# TSC_Project_v21.net
KiCad netlist of a schematic drawn in EAGLE
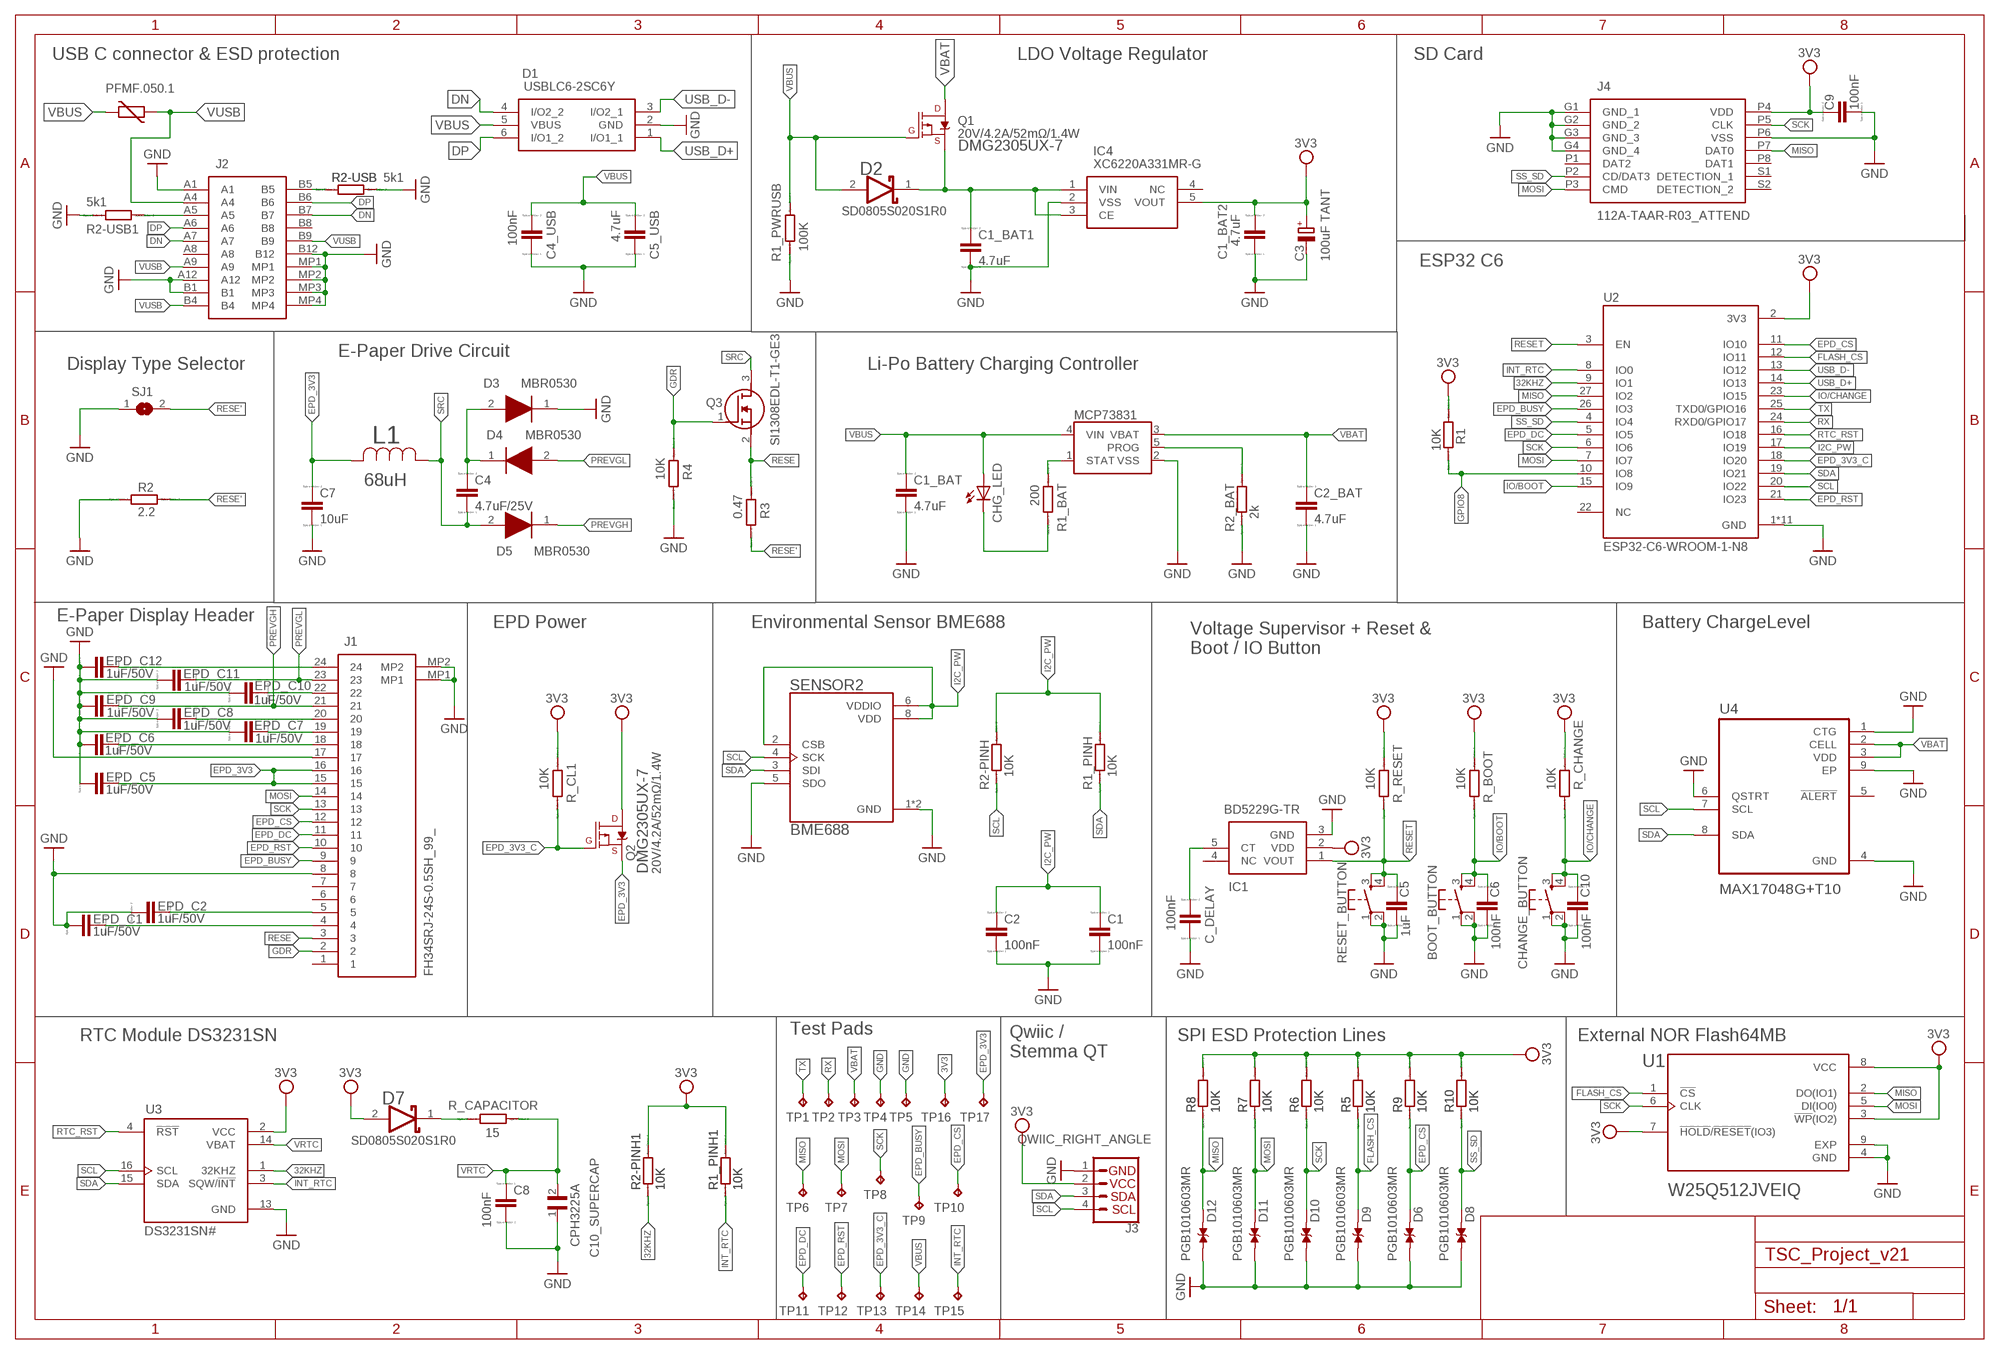
[diagram p0: schematic, sheet 1]

(export (version "E")
  (design (tool "Eeschema 10.0.6"))
  (components
    (comp (ref "BOOT_BUTTON")
      (value "BUTTON_CUSYOMV1")
      (footprint "eagle-import:MYBUTTON")
      (libsource (lib "eagle-import") (part "BUTTON_CUSYOMV1"))
    )
    (comp (ref "C1")
      (value "100nF")
      (footprint "eagle-import:EAGLE-LTSPICE_C0402")
      (libsource (lib "eagle-import") (part "EAGLE-LTSPICE_CC0402"))
    )
    (comp (ref "C1_BAT")
      (value "4.7uF")
      (footprint "eagle-import:EAGLE-LTSPICE_C0402")
      (libsource (lib "eagle-import") (part "EAGLE-LTSPICE_CC0402"))
    )
    (comp (ref "C1_BAT1")
      (value "4.7uF")
      (footprint "eagle-import:EAGLE-LTSPICE_C0402")
      (libsource (lib "eagle-import") (part "EAGLE-LTSPICE_CC0402"))
    )
    (comp (ref "C1_BAT2")
      (value "4.7uF")
      (footprint "eagle-import:EAGLE-LTSPICE_C0402")
      (libsource (lib "eagle-import") (part "EAGLE-LTSPICE_CC0402"))
    )
    (comp (ref "C2")
      (value "100nF")
      (footprint "eagle-import:EAGLE-LTSPICE_C0402")
      (libsource (lib "eagle-import") (part "EAGLE-LTSPICE_CC0402"))
    )
    (comp (ref "C2_BAT")
      (value "4.7uF")
      (footprint "eagle-import:EAGLE-LTSPICE_C0402")
      (libsource (lib "eagle-import") (part "EAGLE-LTSPICE_CC0402"))
    )
    (comp (ref "C3")
      (value "100uF TANT")
      (footprint "eagle-import:RCL_CT3528")
      (libsource (lib "eagle-import") (part "RCL_CPOL-EUCT3528"))
    )
    (comp (ref "C4")
      (value "4.7uF/25V")
      (footprint "eagle-import:EAGLE-LTSPICE_C0402")
      (libsource (lib "eagle-import") (part "EAGLE-LTSPICE_CC0402"))
    )
    (comp (ref "C4_USB")
      (value "100nF")
      (footprint "eagle-import:EAGLE-LTSPICE_C0402")
      (libsource (lib "eagle-import") (part "EAGLE-LTSPICE_CC0402"))
    )
    (comp (ref "C5")
      (value "1uF")
      (footprint "eagle-import:EAGLE-LTSPICE_C0402")
      (libsource (lib "eagle-import") (part "EAGLE-LTSPICE_CC0402"))
    )
    (comp (ref "C5_USB")
      (value "4.7uF")
      (footprint "eagle-import:EAGLE-LTSPICE_C0402")
      (libsource (lib "eagle-import") (part "EAGLE-LTSPICE_CC0402"))
    )
    (comp (ref "C6")
      (value "100nF")
      (footprint "eagle-import:EAGLE-LTSPICE_C0402")
      (libsource (lib "eagle-import") (part "EAGLE-LTSPICE_CC0402"))
    )
    (comp (ref "C7")
      (value "10uF")
      (footprint "eagle-import:EAGLE-LTSPICE_C0402")
      (libsource (lib "eagle-import") (part "EAGLE-LTSPICE_CC0402"))
    )
    (comp (ref "C8")
      (value "100nF")
      (footprint "eagle-import:EAGLE-LTSPICE_C0402")
      (libsource (lib "eagle-import") (part "EAGLE-LTSPICE_CC0402"))
    )
    (comp (ref "C9")
      (value "100nF")
      (footprint "eagle-import:EAGLE-LTSPICE_C0402")
      (libsource (lib "eagle-import") (part "EAGLE-LTSPICE_CC0402"))
    )
    (comp (ref "C10")
      (value "100nF")
      (footprint "eagle-import:EAGLE-LTSPICE_C0402")
      (libsource (lib "eagle-import") (part "EAGLE-LTSPICE_CC0402"))
    )
    (comp (ref "C10_SUPERCAP")
      (value "CPH3225A")
      (footprint "eagle-import:CAPCP3225X100N")
      (fields (field (name "MF") "Seiko Instruments"))
      (libsource (lib "eagle-import") (part "CPH3225A"))
    )
    (comp (ref "CHANGE_BUTTON")
      (value "BUTTON_CUSYOMV1")
      (footprint "eagle-import:MYBUTTON")
      (libsource (lib "eagle-import") (part "BUTTON_CUSYOMV1"))
    )
    (comp (ref "CHG_LED")
      (value "ADAFRUIT_LEDCHIP-LED0603")
      (footprint "eagle-import:ADAFRUIT_CHIP-LED0603")
      (libsource (lib "eagle-import") (part "ADAFRUIT_LEDCHIP-LED0603"))
    )
    (comp (ref "C_DELAY")
      (value "100nF")
      (footprint "eagle-import:EAGLE-LTSPICE_C0402")
      (libsource (lib "eagle-import") (part "EAGLE-LTSPICE_CC0402"))
    )
    (comp (ref "D1")
      (value "USBLC6-2SC6Y")
      (footprint "eagle-import:SOT95P280X145-6N")
      (fields (field (name "MF") "STMicroelectronics"))
      (libsource (lib "eagle-import") (part "USBLC6-2SC6Y"))
    )
    (comp (ref "D2")
      (value "ESP32_WROVER_AVX---SD0805S020S1R0_AVX_SD0805S020S1R0_0_0AVX_SD0805S020S1R0_0_0")
      (footprint "eagle-import:ESP32_WROVER_AVX---SD0805S020S1R0_AVX_SD0805S020S1R0_0")
      (fields
        (field (name "DIGIKEY_PART_NUMBER") "478-7800-1-ND")
        (field (name "MF") "AVX")
        (field (name "MOUSER_PART_NUMBER") "581-SD0805S020S1R0")
        (field (name "SD0805S020S1R0") "SD0805S020S1R0")
      )
      (libsource (lib "eagle-import") (part "ESP32_WROVER_AVX---SD0805S020S1R0_AVX_SD0805S020S1R0_0_0AVX_SD0805S020S1R0_0_0"))
    )
    (comp (ref "D3")
      (value "MBR0530")
      (footprint "eagle-import:SOD3716X135N")
      (fields (field (name "MF") "ON Semiconductor"))
      (libsource (lib "eagle-import") (part "MBR0530"))
    )
    (comp (ref "D4")
      (value "MBR0530")
      (footprint "eagle-import:SOD3716X135N")
      (fields (field (name "MF") "ON Semiconductor"))
      (libsource (lib "eagle-import") (part "MBR0530"))
    )
    (comp (ref "D5")
      (value "MBR0530")
      (footprint "eagle-import:SOD3716X135N")
      (fields (field (name "MF") "ON Semiconductor"))
      (libsource (lib "eagle-import") (part "MBR0530"))
    )
    (comp (ref "D6")
      (value "PGB1010603MR")
      (footprint "eagle-import:DIOC1608X36N")
      (fields (field (name "MF") "Littelfuse Inc."))
      (libsource (lib "eagle-import") (part "PGB1010603MR"))
    )
    (comp (ref "D7")
      (value "ESP32_WROVER_AVX---SD0805S020S1R0_AVX_SD0805S020S1R0_0_0AVX_SD0805S020S1R0_0_0")
      (footprint "eagle-import:ESP32_WROVER_AVX---SD0805S020S1R0_AVX_SD0805S020S1R0_0")
      (fields
        (field (name "DIGIKEY_PART_NUMBER") "478-7800-1-ND")
        (field (name "MF") "AVX")
        (field (name "MOUSER_PART_NUMBER") "581-SD0805S020S1R0")
        (field (name "DIODE") "SD0805S020S1R0")
      )
      (libsource (lib "eagle-import") (part "ESP32_WROVER_AVX---SD0805S020S1R0_AVX_SD0805S020S1R0_0_0AVX_SD0805S020S1R0_0_0"))
    )
    (comp (ref "D8")
      (value "PGB1010603MR")
      (footprint "eagle-import:DIOC1608X36N")
      (fields (field (name "MF") "Littelfuse Inc."))
      (libsource (lib "eagle-import") (part "PGB1010603MR"))
    )
    (comp (ref "D9")
      (value "PGB1010603MR")
      (footprint "eagle-import:DIOC1608X36N")
      (fields (field (name "MF") "Littelfuse Inc."))
      (libsource (lib "eagle-import") (part "PGB1010603MR"))
    )
    (comp (ref "D10")
      (value "PGB1010603MR")
      (footprint "eagle-import:DIOC1608X36N")
      (fields (field (name "MF") "Littelfuse Inc."))
      (libsource (lib "eagle-import") (part "PGB1010603MR"))
    )
    (comp (ref "D11")
      (value "PGB1010603MR")
      (footprint "eagle-import:DIOC1608X36N")
      (fields (field (name "MF") "Littelfuse Inc."))
      (libsource (lib "eagle-import") (part "PGB1010603MR"))
    )
    (comp (ref "D12")
      (value "PGB1010603MR")
      (footprint "eagle-import:DIOC1608X36N")
      (fields (field (name "MF") "Littelfuse Inc."))
      (libsource (lib "eagle-import") (part "PGB1010603MR"))
    )
    (comp (ref "EPD_C1")
      (value "1uF/50V")
      (footprint "eagle-import:EAGLE-LTSPICE_C0402")
      (libsource (lib "eagle-import") (part "EAGLE-LTSPICE_CC0402"))
    )
    (comp (ref "EPD_C2")
      (value "1uF/50V")
      (footprint "eagle-import:EAGLE-LTSPICE_C0402")
      (libsource (lib "eagle-import") (part "EAGLE-LTSPICE_CC0402"))
    )
    (comp (ref "EPD_C5")
      (value "1uF/50V")
      (footprint "eagle-import:EAGLE-LTSPICE_C0402")
      (libsource (lib "eagle-import") (part "EAGLE-LTSPICE_CC0402"))
    )
    (comp (ref "EPD_C6")
      (value "1uF/50V")
      (footprint "eagle-import:EAGLE-LTSPICE_C0402")
      (libsource (lib "eagle-import") (part "EAGLE-LTSPICE_CC0402"))
    )
    (comp (ref "EPD_C7")
      (value "1uF/50V")
      (footprint "eagle-import:EAGLE-LTSPICE_C0402")
      (libsource (lib "eagle-import") (part "EAGLE-LTSPICE_CC0402"))
    )
    (comp (ref "EPD_C8")
      (value "1uF/50V")
      (footprint "eagle-import:EAGLE-LTSPICE_C0402")
      (libsource (lib "eagle-import") (part "EAGLE-LTSPICE_CC0402"))
    )
    (comp (ref "EPD_C9")
      (value "1uF/50V")
      (footprint "eagle-import:EAGLE-LTSPICE_C0402")
      (libsource (lib "eagle-import") (part "EAGLE-LTSPICE_CC0402"))
    )
    (comp (ref "EPD_C10")
      (value "1uF/50V")
      (footprint "eagle-import:EAGLE-LTSPICE_C0402")
      (libsource (lib "eagle-import") (part "EAGLE-LTSPICE_CC0402"))
    )
    (comp (ref "EPD_C11")
      (value "1uF/50V")
      (footprint "eagle-import:EAGLE-LTSPICE_C0402")
      (libsource (lib "eagle-import") (part "EAGLE-LTSPICE_CC0402"))
    )
    (comp (ref "EPD_C12")
      (value "1uF/50V")
      (footprint "eagle-import:EAGLE-LTSPICE_C0402")
      (libsource (lib "eagle-import") (part "EAGLE-LTSPICE_CC0402"))
    )
    (comp (ref "IC1")
      (value "BD5229G-TR")
      (footprint "eagle-import:SOT95P280X125-5N")
      (fields (field (name "MOUSER_PART_NUMBER") "755-BD5229G-TR"))
      (libsource (lib "eagle-import") (part "BD5229G-TR"))
    )
    (comp (ref "IC4")
      (value "XC6220A331MR-G")
      (footprint "eagle-import:SOT95P280X120-5N")
      (fields (field (name "MOUSER_PART_NUMBER") "865-XC6220A331MR-G"))
      (libsource (lib "eagle-import") (part "XC6220A331MR-G"))
    )
    (comp (ref "J1")
      (value "FH34SRJ-24S-0.5SH_99_")
      (footprint "eagle-import:FH34SRJ24S05SH99")
      (fields
        (field (name "MANUFACTURER_PART_NUMBER") "FH34SRJ-24S-0.5SH(99)")
        (field (name "MOUSER_PART_NUMBER") "798-FH34SRJ24S05SH99")
      )
      (libsource (lib "eagle-import") (part "FH34SRJ-24S-0.5SH_99_"))
    )
    (comp (ref "J2")
      (value "SAMACSYS_PARTS_USB4110-GF-A")
      (footprint "eagle-import:SAMACSYS_PARTS_USB4110GFA")
      (fields
        (field (name "MANUFACTURER_PART_NUMBER") "USB4110-GF-A")
        (field (name "MOUSER_PART_NUMBER") "640-USB4110-GF-A")
      )
      (libsource (lib "eagle-import") (part "SAMACSYS_PARTS_USB4110-GF-A"))
    )
    (comp (ref "J3")
      (value "QWIIC_RIGHT_ANGLE")
      (footprint "eagle-import:JST04_1MM_RA")
      (libsource (lib "eagle-import") (part "QWIIC_CONNECTORJS-1MM"))
    )
    (comp (ref "J4")
      (value "112A-TAAR-R03_ATTEND")
      (footprint "eagle-import:112ATAARR03ATTEND")
      (fields (field (name "MANUFACTURER_PART_NUMBER") "112A-TAAR-R03 ATTEND"))
      (libsource (lib "eagle-import") (part "112A-TAAR-R03_ATTEND"))
    )
    (comp (ref "L1")
      (value "744043680IND_4828-WE-TPC_WRE")
      (footprint "eagle-import:IND_4828-WE-TPC_WRE")
      (fields
        (field (name "MANUFACTURER_PART_NUMBER") "744043680")
        (field (name "L1") "68uH")
        (field (name "COPYRIGHT") "Copyright (C) 2024 Ultra Librarian. All rights reserved.")
      )
      (libsource (lib "eagle-import") (part "744043680IND_4828-WE-TPC_WRE"))
    )
    (comp (ref "MCP73831")
      (value "ESP32_WROVER_SPARKFUN-IC-POWER_MCP73831")
      (footprint "eagle-import:ESP32_WROVER_SPARKFUN-IC-POWER_SOT23-5")
      (libsource (lib "eagle-import") (part "ESP32_WROVER_SPARKFUN-IC-POWER_MCP73831"))
    )
    (comp (ref "PFMF.050.1")
      (value "ESP32C6_VARISTORCN1812")
      (footprint "eagle-import:ESP32C6_VARISTOR_CT_CN1812")
      (libsource (lib "eagle-import") (part "ESP32C6_VARISTORCN1812"))
    )
    (comp (ref "Q1")
      (value "20V/4.2A/52mΩ/1.4W")
      (footprint "eagle-import:ESP32_WROVER_SPARKFUN-DISCRETESEMI_SOT23-3")
      (libsource (lib "eagle-import") (part "ESP32_WROVER_SPARKFUN-DISCRETESEMI_MOSFET_PCH-DMG2305UX-7"))
    )
    (comp (ref "Q2")
      (value "20V/4.2A/52mΩ/1.4W")
      (footprint "eagle-import:ESP32_WROVER_SPARKFUN-DISCRETESEMI_SOT23-3")
      (libsource (lib "eagle-import") (part "ESP32_WROVER_SPARKFUN-DISCRETESEMI_MOSFET_PCH-DMG2305UX-7"))
    )
    (comp (ref "Q3")
      (value "SI1308EDL-T1-GE3")
      (footprint "eagle-import:SOT65P210X110-3N")
      (fields (field (name "MF") "Vishay Siliconix"))
      (libsource (lib "eagle-import") (part "SI1308EDL-T1-GE3"))
    )
    (comp (ref "R1")
      (value "10K")
      (footprint "eagle-import:ESP32_WROVER_EAGLE-LTSPICE_R0402")
      (libsource (lib "eagle-import") (part "ESP32_WROVER_EAGLE-LTSPICE_RR0402"))
    )
    (comp (ref "R1_BAT")
      (value "200")
      (footprint "eagle-import:ESP32_WROVER_EAGLE-LTSPICE_R0402")
      (libsource (lib "eagle-import") (part "ESP32_WROVER_EAGLE-LTSPICE_RR0402"))
    )
    (comp (ref "R1_PINH")
      (value "10K")
      (footprint "eagle-import:ESP32_WROVER_EAGLE-LTSPICE_R0402")
      (libsource (lib "eagle-import") (part "ESP32_WROVER_EAGLE-LTSPICE_RR0402"))
    )
    (comp (ref "R1_PINH1")
      (value "10K")
      (footprint "eagle-import:ESP32_WROVER_EAGLE-LTSPICE_R0402")
      (libsource (lib "eagle-import") (part "ESP32_WROVER_EAGLE-LTSPICE_RR0402"))
    )
    (comp (ref "R1_PWRUSB")
      (value "100K")
      (footprint "eagle-import:ESP32_WROVER_EAGLE-LTSPICE_R0402")
      (libsource (lib "eagle-import") (part "ESP32_WROVER_EAGLE-LTSPICE_RR0402"))
    )
    (comp (ref "R2")
      (value "2.2")
      (footprint "eagle-import:ESP32_WROVER_EAGLE-LTSPICE_R0402")
      (libsource (lib "eagle-import") (part "ESP32_WROVER_EAGLE-LTSPICE_RR0402"))
    )
    (comp (ref "R2-PINH")
      (value "10K")
      (footprint "eagle-import:ESP32_WROVER_EAGLE-LTSPICE_R0402")
      (libsource (lib "eagle-import") (part "ESP32_WROVER_EAGLE-LTSPICE_RR0402"))
    )
    (comp (ref "R2-PINH1")
      (value "10K")
      (footprint "eagle-import:ESP32_WROVER_EAGLE-LTSPICE_R0402")
      (libsource (lib "eagle-import") (part "ESP32_WROVER_EAGLE-LTSPICE_RR0402"))
    )
    (comp (ref "R2-USB")
      (value "5k1")
      (footprint "eagle-import:ESP32_WROVER_EAGLE-LTSPICE_R0402")
      (libsource (lib "eagle-import") (part "ESP32_WROVER_EAGLE-LTSPICE_RR0402"))
    )
    (comp (ref "R2-USB1")
      (value "5k1")
      (footprint "eagle-import:ESP32_WROVER_EAGLE-LTSPICE_R0402")
      (libsource (lib "eagle-import") (part "ESP32_WROVER_EAGLE-LTSPICE_RR0402"))
    )
    (comp (ref "R2_BAT")
      (value "2k")
      (footprint "eagle-import:ESP32_WROVER_EAGLE-LTSPICE_R0402")
      (libsource (lib "eagle-import") (part "ESP32_WROVER_EAGLE-LTSPICE_RR0402"))
    )
    (comp (ref "R3")
      (value "0.47")
      (footprint "eagle-import:ESP32_WROVER_EAGLE-LTSPICE_R0402")
      (libsource (lib "eagle-import") (part "ESP32_WROVER_EAGLE-LTSPICE_RR0402"))
    )
    (comp (ref "R4")
      (value "10K")
      (footprint "eagle-import:ESP32_WROVER_EAGLE-LTSPICE_R0402")
      (libsource (lib "eagle-import") (part "ESP32_WROVER_EAGLE-LTSPICE_RR0402"))
    )
    (comp (ref "R5")
      (value "10K")
      (footprint "eagle-import:ESP32_WROVER_EAGLE-LTSPICE_R0402")
      (libsource (lib "eagle-import") (part "ESP32_WROVER_EAGLE-LTSPICE_RR0402"))
    )
    (comp (ref "R6")
      (value "10K")
      (footprint "eagle-import:ESP32_WROVER_EAGLE-LTSPICE_R0402")
      (libsource (lib "eagle-import") (part "ESP32_WROVER_EAGLE-LTSPICE_RR0402"))
    )
    (comp (ref "R7")
      (value "10K")
      (footprint "eagle-import:ESP32_WROVER_EAGLE-LTSPICE_R0402")
      (libsource (lib "eagle-import") (part "ESP32_WROVER_EAGLE-LTSPICE_RR0402"))
    )
    (comp (ref "R8")
      (value "10K")
      (footprint "eagle-import:ESP32_WROVER_EAGLE-LTSPICE_R0402")
      (libsource (lib "eagle-import") (part "ESP32_WROVER_EAGLE-LTSPICE_RR0402"))
    )
    (comp (ref "R9")
      (value "10K")
      (footprint "eagle-import:ESP32_WROVER_EAGLE-LTSPICE_R0402")
      (libsource (lib "eagle-import") (part "ESP32_WROVER_EAGLE-LTSPICE_RR0402"))
    )
    (comp (ref "R10")
      (value "10K")
      (footprint "eagle-import:ESP32_WROVER_EAGLE-LTSPICE_R0402")
      (libsource (lib "eagle-import") (part "ESP32_WROVER_EAGLE-LTSPICE_RR0402"))
    )
    (comp (ref "RESET_BUTTON")
      (value "BUTTON_CUSYOMV1")
      (footprint "eagle-import:MYBUTTON")
      (libsource (lib "eagle-import") (part "BUTTON_CUSYOMV1"))
    )
    (comp (ref "R_BOOT")
      (value "10K")
      (footprint "eagle-import:ESP32_WROVER_EAGLE-LTSPICE_R0402")
      (libsource (lib "eagle-import") (part "ESP32_WROVER_EAGLE-LTSPICE_RR0402"))
    )
    (comp (ref "R_CAPACITOR")
      (value "15")
      (footprint "eagle-import:ESP32_WROVER_EAGLE-LTSPICE_R0402")
      (libsource (lib "eagle-import") (part "ESP32_WROVER_EAGLE-LTSPICE_RR0402"))
    )
    (comp (ref "R_CHANGE")
      (value "10K")
      (footprint "eagle-import:ESP32_WROVER_EAGLE-LTSPICE_R0402")
      (libsource (lib "eagle-import") (part "ESP32_WROVER_EAGLE-LTSPICE_RR0402"))
    )
    (comp (ref "R_CL1")
      (value "10K")
      (footprint "eagle-import:ESP32_WROVER_EAGLE-LTSPICE_R0402")
      (libsource (lib "eagle-import") (part "ESP32_WROVER_EAGLE-LTSPICE_RR0402"))
    )
    (comp (ref "R_RESET")
      (value "10K")
      (footprint "eagle-import:ESP32_WROVER_EAGLE-LTSPICE_R0402")
      (libsource (lib "eagle-import") (part "ESP32_WROVER_EAGLE-LTSPICE_RR0402"))
    )
    (comp (ref "SENSOR2")
      (value "ESP32_WROVER_BME680_BME680")
      (footprint "eagle-import:ESP32_WROVER_BME680_PSON80P300X300X100-8N")
      (fields
        (field (name "MF") "Bosch Sensortec")
        (field (name "MP") "BME680")
        (field (name "MP1") "BME688")
      )
      (libsource (lib "eagle-import") (part "ESP32_WROVER_BME680_BME680"))
    )
    (comp (ref "SJ1") (value "SJ") (footprint "eagle-import:SJ") (libsource (lib "eagle-import") (part "SJ")))
    (comp (ref "TP1")
      (value "TPTP20R")
      (footprint "eagle-import:TP20R")
      (libsource (lib "eagle-import") (part "TPTP20R"))
    )
    (comp (ref "TP2")
      (value "TPTP20R")
      (footprint "eagle-import:TP20R")
      (libsource (lib "eagle-import") (part "TPTP20R"))
    )
    (comp (ref "TP3")
      (value "TPTP20R")
      (footprint "eagle-import:TP20R")
      (libsource (lib "eagle-import") (part "TPTP20R"))
    )
    (comp (ref "TP4")
      (value "TPTP20R")
      (footprint "eagle-import:TP20R")
      (libsource (lib "eagle-import") (part "TPTP20R"))
    )
    (comp (ref "TP5")
      (value "TPTP20R")
      (footprint "eagle-import:TP20R")
      (libsource (lib "eagle-import") (part "TPTP20R"))
    )
    (comp (ref "TP6")
      (value "TPTP20R")
      (footprint "eagle-import:TP20R")
      (libsource (lib "eagle-import") (part "TPTP20R"))
    )
    (comp (ref "TP7")
      (value "TPTP20R")
      (footprint "eagle-import:TP20R")
      (libsource (lib "eagle-import") (part "TPTP20R"))
    )
    (comp (ref "TP8")
      (value "TPTP20R")
      (footprint "eagle-import:TP20R")
      (libsource (lib "eagle-import") (part "TPTP20R"))
    )
    (comp (ref "TP9")
      (value "TPTP20R")
      (footprint "eagle-import:TP20R")
      (libsource (lib "eagle-import") (part "TPTP20R"))
    )
    (comp (ref "TP10")
      (value "TPTP20R")
      (footprint "eagle-import:TP20R")
      (libsource (lib "eagle-import") (part "TPTP20R"))
    )
    (comp (ref "TP11")
      (value "TPTP20R")
      (footprint "eagle-import:TP20R")
      (libsource (lib "eagle-import") (part "TPTP20R"))
    )
    (comp (ref "TP12")
      (value "TPTP20R")
      (footprint "eagle-import:TP20R")
      (libsource (lib "eagle-import") (part "TPTP20R"))
    )
    (comp (ref "TP13")
      (value "TPTP20R")
      (footprint "eagle-import:TP20R")
      (libsource (lib "eagle-import") (part "TPTP20R"))
    )
    (comp (ref "TP14")
      (value "TPTP20R")
      (footprint "eagle-import:TP20R")
      (libsource (lib "eagle-import") (part "TPTP20R"))
    )
    (comp (ref "TP15")
      (value "TPTP20R")
      (footprint "eagle-import:TP20R")
      (libsource (lib "eagle-import") (part "TPTP20R"))
    )
    (comp (ref "TP16")
      (value "TPTP20R")
      (footprint "eagle-import:TP20R")
      (libsource (lib "eagle-import") (part "TPTP20R"))
    )
    (comp (ref "TP17")
      (value "TPTP20R")
      (footprint "eagle-import:TP20R")
      (libsource (lib "eagle-import") (part "TPTP20R"))
    )
    (comp (ref "U1")
      (value "W25Q512JVEIQ")
      (footprint "eagle-import:SON127P600X800X80-9N")
      (fields (field (name "MF") "Winbond Electronics"))
      (libsource (lib "eagle-import") (part "W25Q512JVEIQ"))
    )
    (comp (ref "U2")
      (value "ESP32-C6-WROOM-1-N8")
      (footprint "eagle-import:XCVR_ESP32-C6-WROOM-1-N8")
      (fields (field (name "MF") "Espressif Systems"))
      (libsource (lib "eagle-import") (part "ESP32-C6-WROOM-1-N8"))
    )
    (comp (ref "U3")
      (value "DS3231SN#")
      (footprint "eagle-import:SOIC127P1032X265-16N")
      (fields (field (name "MF") "Analog Devices"))
      (libsource (lib "eagle-import") (part "DS3231SN#"))
    )
    (comp (ref "U4")
      (value "MAX17048G+T10")
      (footprint "eagle-import:SON50P200X200X80-9N")
      (fields (field (name "MF") "Analog Devices"))
      (libsource (lib "eagle-import") (part "MAX17048G+T10"))
    )
  )
  (nets
    (net (code "1") (name "3V3") (class "Default")
      (node (ref "C1_BAT2") (pin "2") (pinfunction "2_2") (pintype "passive"))
      (node (ref "C3") (pin "+") (pinfunction "+_+") (pintype "passive"))
      (node (ref "C9") (pin "2") (pinfunction "2_2") (pintype "passive"))
      (node (ref "D7") (pin "2") (pinfunction "ANODE_2") (pintype "bidirectional"))
      (node (ref "IC1") (pin "2") (pinfunction "VDD_2") (pintype "bidirectional"))
      (node (ref "IC4") (pin "5") (pinfunction "VOUT_5") (pintype "bidirectional"))
      (node (ref "J3") (pin "2") (pinfunction "2_2") (pintype "power_in"))
      (node (ref "J4") (pin "P4") (pinfunction "VDD_P4") (pintype "bidirectional"))
      (node (ref "Q2") (pin "3") (pinfunction "D_3") (pintype "bidirectional"))
      (node (ref "R1") (pin "1") (pinfunction "1_1") (pintype "passive"))
      (node (ref "R10") (pin "2") (pinfunction "2_2") (pintype "passive"))
      (node (ref "R1_PINH1") (pin "2") (pinfunction "2_2") (pintype "passive"))
      (node (ref "R2-PINH1") (pin "2") (pinfunction "2_2") (pintype "passive"))
      (node (ref "R5") (pin "2") (pinfunction "2_2") (pintype "passive"))
      (node (ref "R6") (pin "2") (pinfunction "2_2") (pintype "passive"))
      (node (ref "R7") (pin "2") (pinfunction "2_2") (pintype "passive"))
      (node (ref "R8") (pin "2") (pinfunction "2_2") (pintype "passive"))
      (node (ref "R9") (pin "2") (pinfunction "2_2") (pintype "passive"))
      (node (ref "R_BOOT") (pin "2") (pinfunction "2_2") (pintype "passive"))
      (node (ref "R_CHANGE") (pin "2") (pinfunction "2_2") (pintype "passive"))
      (node (ref "R_CL1") (pin "2") (pinfunction "2_2") (pintype "passive"))
      (node (ref "R_RESET") (pin "2") (pinfunction "2_2") (pintype "passive"))
      (node (ref "TP16") (pin "TP") (pinfunction "TP_TP") (pintype "input"))
      (node (ref "U1") (pin "3") (pinfunction "~{WP}(IO2)_3") (pintype "bidirectional"))
      (node (ref "U1") (pin "7") (pinfunction "~{HOLD}/~{RESET}(IO3)_7") (pintype "bidirectional"))
      (node (ref "U1") (pin "8") (pinfunction "VCC_8") (pintype "power_in"))
      (node (ref "U2") (pin "2") (pinfunction "3V3_2") (pintype "power_in"))
      (node (ref "U3") (pin "2") (pinfunction "VCC_2") (pintype "power_in"))
    )
    (net (code "2") (name "32KHZ") (class "Default")
      (node (ref "R2-PINH1") (pin "1") (pinfunction "1_1") (pintype "passive"))
      (node (ref "U2") (pin "9") (pinfunction "IO1_9") (pintype "bidirectional"))
      (node (ref "U3") (pin "1") (pinfunction "32KHZ_1") (pintype "output"))
    )
    (net (code "3") (name "DN") (class "Default")
      (node (ref "D1") (pin "4") (pinfunction "I/O2_2_4") (pintype "bidirectional"))
      (node (ref "J2") (pin "A7") (pinfunction "A7_A7") (pintype "bidirectional"))
      (node (ref "J2") (pin "B7") (pinfunction "B7_B7") (pintype "bidirectional"))
    )
    (net (code "4") (name "DP") (class "Default")
      (node (ref "D1") (pin "6") (pinfunction "I/O1_2_6") (pintype "bidirectional"))
      (node (ref "J2") (pin "A6") (pinfunction "A6_A6") (pintype "bidirectional"))
      (node (ref "J2") (pin "B6") (pinfunction "B6_B6") (pintype "bidirectional"))
    )
    (net (code "5") (name "EPD_3V3") (class "Default")
      (node (ref "C7") (pin "2") (pinfunction "2_2") (pintype "passive"))
      (node (ref "EPD_C5") (pin "1") (pinfunction "1_1") (pintype "passive"))
      (node (ref "J1") (pin "15") (pinfunction "15_15") (pintype "bidirectional"))
      (node (ref "J1") (pin "16") (pinfunction "16_16") (pintype "bidirectional"))
      (node (ref "L1") (pin "2") (pinfunction "2_2") (pintype "passive"))
      (node (ref "Q2") (pin "2") (pinfunction "S_2") (pintype "bidirectional"))
      (node (ref "TP17") (pin "TP") (pinfunction "TP_TP") (pintype "input"))
    )
    (net (code "6") (name "EPD_3V3_C") (class "Default")
      (node (ref "Q2") (pin "1") (pinfunction "G_1") (pintype "bidirectional"))
      (node (ref "R_CL1") (pin "1") (pinfunction "1_1") (pintype "passive"))
      (node (ref "TP13") (pin "TP") (pinfunction "TP_TP") (pintype "input"))
      (node (ref "U2") (pin "18") (pinfunction "IO20_18") (pintype "bidirectional"))
    )
    (net (code "7") (name "EPD_BUSY") (class "Default")
      (node (ref "J1") (pin "9") (pinfunction "9_9") (pintype "bidirectional"))
      (node (ref "TP9") (pin "TP") (pinfunction "TP_TP") (pintype "input"))
      (node (ref "U2") (pin "26") (pinfunction "IO3_26") (pintype "bidirectional"))
    )
    (net (code "8") (name "EPD_CS") (class "Default")
      (node (ref "D6") (pin "2") (pinfunction "2_2") (pintype "passive"))
      (node (ref "J1") (pin "12") (pinfunction "12_12") (pintype "bidirectional"))
      (node (ref "R9") (pin "1") (pinfunction "1_1") (pintype "passive"))
      (node (ref "TP10") (pin "TP") (pinfunction "TP_TP") (pintype "input"))
      (node (ref "U2") (pin "11") (pinfunction "IO10_11") (pintype "bidirectional"))
    )
    (net (code "9") (name "EPD_DC") (class "Default")
      (node (ref "J1") (pin "11") (pinfunction "11_11") (pintype "bidirectional"))
      (node (ref "TP11") (pin "TP") (pinfunction "TP_TP") (pintype "input"))
      (node (ref "U2") (pin "5") (pinfunction "IO5_5") (pintype "bidirectional"))
    )
    (net (code "10") (name "EPD_RST") (class "Default")
      (node (ref "J1") (pin "10") (pinfunction "10_10") (pintype "bidirectional"))
      (node (ref "TP12") (pin "TP") (pinfunction "TP_TP") (pintype "input"))
      (node (ref "U2") (pin "21") (pinfunction "IO23_21") (pintype "bidirectional"))
    )
    (net (code "11") (name "FLASH_CS") (class "Default")
      (node (ref "D9") (pin "2") (pinfunction "2_2") (pintype "passive"))
      (node (ref "R5") (pin "1") (pinfunction "1_1") (pintype "passive"))
      (node (ref "U1") (pin "1") (pinfunction "~{CS}_1") (pintype "input"))
      (node (ref "U2") (pin "12") (pinfunction "IO11_12") (pintype "bidirectional"))
    )
    (net (code "12") (name "GDR") (class "Default")
      (node (ref "J1") (pin "2") (pinfunction "2_2") (pintype "bidirectional"))
      (node (ref "Q3") (pin "1") (pinfunction "G_1") (pintype "bidirectional"))
      (node (ref "R4") (pin "2") (pinfunction "2_2") (pintype "passive"))
    )
    (net (code "13") (name "GND") (class "Default")
      (node (ref "BOOT_BUTTON") (pin "1") (pinfunction "1_1") (pintype "passive"))
      (node (ref "BOOT_BUTTON") (pin "2") (pinfunction "2_2") (pintype "passive"))
      (node (ref "C1") (pin "1") (pinfunction "1_1") (pintype "passive"))
      (node (ref "C10") (pin "1") (pinfunction "1_1") (pintype "passive"))
      (node (ref "C10_SUPERCAP") (pin "1") (pinfunction "1_1") (pintype "passive"))
      (node (ref "C1_BAT") (pin "1") (pinfunction "1_1") (pintype "passive"))
      (node (ref "C1_BAT1") (pin "1") (pinfunction "1_1") (pintype "passive"))
      (node (ref "C1_BAT2") (pin "1") (pinfunction "1_1") (pintype "passive"))
      (node (ref "C2") (pin "1") (pinfunction "1_1") (pintype "passive"))
      (node (ref "C2_BAT") (pin "1") (pinfunction "1_1") (pintype "passive"))
      (node (ref "C3") (pin "-") (pinfunction "-_-") (pintype "passive"))
      (node (ref "C4_USB") (pin "1") (pinfunction "1_1") (pintype "passive"))
      (node (ref "C5") (pin "1") (pinfunction "1_1") (pintype "passive"))
      (node (ref "C5_USB") (pin "1") (pinfunction "1_1") (pintype "passive"))
      (node (ref "C6") (pin "1") (pinfunction "1_1") (pintype "passive"))
      (node (ref "C7") (pin "1") (pinfunction "1_1") (pintype "passive"))
      (node (ref "C8") (pin "2") (pinfunction "2_2") (pintype "passive"))
      (node (ref "C9") (pin "1") (pinfunction "1_1") (pintype "passive"))
      (node (ref "CHANGE_BUTTON") (pin "1") (pinfunction "1_1") (pintype "passive"))
      (node (ref "CHANGE_BUTTON") (pin "2") (pinfunction "2_2") (pintype "passive"))
      (node (ref "C_DELAY") (pin "1") (pinfunction "1_1") (pintype "passive"))
      (node (ref "D1") (pin "2") (pinfunction "GND_2") (pintype "bidirectional"))
      (node (ref "D10") (pin "1") (pinfunction "1_1") (pintype "passive"))
      (node (ref "D11") (pin "1") (pinfunction "1_1") (pintype "passive"))
      (node (ref "D12") (pin "1") (pinfunction "1_1") (pintype "passive"))
      (node (ref "D3") (pin "1") (pinfunction "K_1") (pintype "bidirectional"))
      (node (ref "D6") (pin "1") (pinfunction "1_1") (pintype "passive"))
      (node (ref "D8") (pin "1") (pinfunction "1_1") (pintype "passive"))
      (node (ref "D9") (pin "1") (pinfunction "1_1") (pintype "passive"))
      (node (ref "EPD_C1") (pin "2") (pinfunction "2_2") (pintype "passive"))
      (node (ref "EPD_C10") (pin "2") (pinfunction "2_2") (pintype "passive"))
      (node (ref "EPD_C11") (pin "2") (pinfunction "2_2") (pintype "passive"))
      (node (ref "EPD_C12") (pin "2") (pinfunction "2_2") (pintype "passive"))
      (node (ref "EPD_C2") (pin "2") (pinfunction "2_2") (pintype "passive"))
      (node (ref "EPD_C5") (pin "2") (pinfunction "2_2") (pintype "passive"))
      (node (ref "EPD_C6") (pin "2") (pinfunction "2_2") (pintype "passive"))
      (node (ref "EPD_C7") (pin "2") (pinfunction "2_2") (pintype "passive"))
      (node (ref "EPD_C8") (pin "2") (pinfunction "2_2") (pintype "passive"))
      (node (ref "EPD_C9") (pin "2") (pinfunction "2_2") (pintype "passive"))
      (node (ref "IC1") (pin "3") (pinfunction "GND_3") (pintype "bidirectional"))
      (node (ref "IC4") (pin "2") (pinfunction "VSS_2") (pintype "bidirectional"))
      (node (ref "J1") (pin "17") (pinfunction "17_17") (pintype "bidirectional"))
      (node (ref "J1") (pin "8") (pinfunction "8_8") (pintype "bidirectional"))
      (node (ref "J1") (pin "MP1") (pinfunction "MP1_MP1") (pintype "bidirectional"))
      (node (ref "J1") (pin "MP2") (pinfunction "MP2_MP2") (pintype "bidirectional"))
      (node (ref "J2") (pin "A1") (pinfunction "A1_A1") (pintype "bidirectional"))
      (node (ref "J2") (pin "A12") (pinfunction "A12_A12") (pintype "bidirectional"))
      (node (ref "J2") (pin "B1") (pinfunction "B1_B1") (pintype "bidirectional"))
      (node (ref "J2") (pin "B12") (pinfunction "B12_B12") (pintype "bidirectional"))
      (node (ref "J2") (pin "MP1") (pinfunction "MP1_MP1") (pintype "bidirectional"))
      (node (ref "J2") (pin "MP2") (pinfunction "MP2_MP2") (pintype "bidirectional"))
      (node (ref "J2") (pin "MP3") (pinfunction "MP3_MP3") (pintype "bidirectional"))
      (node (ref "J2") (pin "MP4") (pinfunction "MP4_MP4") (pintype "bidirectional"))
      (node (ref "J3") (pin "1") (pinfunction "1_1") (pintype "power_in"))
      (node (ref "J4") (pin "G1") (pinfunction "GND_1_G1") (pintype "bidirectional"))
      (node (ref "J4") (pin "G2") (pinfunction "GND_2_G2") (pintype "bidirectional"))
      (node (ref "J4") (pin "G3") (pinfunction "GND_3_G3") (pintype "bidirectional"))
      (node (ref "J4") (pin "G4") (pinfunction "GND_4_G4") (pintype "bidirectional"))
      (node (ref "J4") (pin "P6") (pinfunction "VSS_P6") (pintype "bidirectional"))
      (node (ref "MCP73831") (pin "2") (pinfunction "VSS_2") (pintype "power_in"))
      (node (ref "R1_PWRUSB") (pin "2") (pinfunction "2_2") (pintype "passive"))
      (node (ref "R2") (pin "1") (pinfunction "1_1") (pintype "passive"))
      (node (ref "R2-USB") (pin "2") (pinfunction "2_2") (pintype "passive"))
      (node (ref "R2-USB1") (pin "1") (pinfunction "1_1") (pintype "passive"))
      (node (ref "R2_BAT") (pin "1") (pinfunction "1_1") (pintype "passive"))
      (node (ref "R4") (pin "1") (pinfunction "1_1") (pintype "passive"))
      (node (ref "RESET_BUTTON") (pin "1") (pinfunction "1_1") (pintype "passive"))
      (node (ref "RESET_BUTTON") (pin "2") (pinfunction "2_2") (pintype "passive"))
      (node (ref "SENSOR2") (pin "1") (pinfunction "GND_1") (pintype "power_in"))
      (node (ref "SENSOR2") (pin "5") (pinfunction "SDO_5") (pintype "bidirectional"))
      (node (ref "SENSOR2") (pin "7") (pinfunction "GND_7") (pintype "power_in"))
      (node (ref "SJ1") (pin "1") (pinfunction "1_1") (pintype "passive"))
      (node (ref "TP4") (pin "TP") (pinfunction "TP_TP") (pintype "input"))
      (node (ref "TP5") (pin "TP") (pinfunction "TP_TP") (pintype "input"))
      (node (ref "U1") (pin "4") (pinfunction "GND_4") (pintype "power_in"))
      (node (ref "U1") (pin "9") (pinfunction "EXP_9") (pintype "passive"))
      (node (ref "U2") (pin "1") (pinfunction "GND_1") (pintype "power_in"))
      (node (ref "U2") (pin "28") (pinfunction "GND_28") (pintype "power_in"))
      (node (ref "U2") (pin "29_1") (pinfunction "GND_29_1") (pintype "power_in"))
      (node (ref "U2") (pin "29_2") (pinfunction "GND_29_2") (pintype "power_in"))
      (node (ref "U2") (pin "29_3") (pinfunction "GND_29_3") (pintype "power_in"))
      (node (ref "U2") (pin "29_4") (pinfunction "GND_29_4") (pintype "power_in"))
      (node (ref "U2") (pin "29_5") (pinfunction "GND_29_5") (pintype "power_in"))
      (node (ref "U2") (pin "29_6") (pinfunction "GND_29_6") (pintype "power_in"))
      (node (ref "U2") (pin "29_7") (pinfunction "GND_29_7") (pintype "power_in"))
      (node (ref "U2") (pin "29_8") (pinfunction "GND_29_8") (pintype "power_in"))
      (node (ref "U2") (pin "29_9") (pinfunction "GND_29_9") (pintype "power_in"))
      (node (ref "U3") (pin "13") (pinfunction "GND_13") (pintype "power_in"))
      (node (ref "U4") (pin "1") (pinfunction "CTG_1") (pintype "power_in"))
      (node (ref "U4") (pin "4") (pinfunction "GND_4") (pintype "power_in"))
      (node (ref "U4") (pin "6") (pinfunction "QSTRT_6") (pintype "input"))
      (node (ref "U4") (pin "9") (pinfunction "EP_9") (pintype "power_in"))
    )
    (net (code "14") (name "GPIO8") (class "Default")
      (node (ref "R1") (pin "2") (pinfunction "2_2") (pintype "passive"))
      (node (ref "U2") (pin "10") (pinfunction "IO8_10") (pintype "bidirectional"))
    )
    (net (code "15") (name "I2C_PW") (class "Default")
      (node (ref "C1") (pin "2") (pinfunction "2_2") (pintype "passive"))
      (node (ref "C2") (pin "2") (pinfunction "2_2") (pintype "passive"))
      (node (ref "R1_PINH") (pin "2") (pinfunction "2_2") (pintype "passive"))
      (node (ref "R2-PINH") (pin "2") (pinfunction "2_2") (pintype "passive"))
      (node (ref "SENSOR2") (pin "2") (pinfunction "CSB_2") (pintype "input"))
      (node (ref "SENSOR2") (pin "6") (pinfunction "VDDIO_6") (pintype "power_in"))
      (node (ref "SENSOR2") (pin "8") (pinfunction "VDD_8") (pintype "power_in"))
      (node (ref "U2") (pin "17") (pinfunction "IO19_17") (pintype "bidirectional"))
    )
    (net (code "16") (name "INT_RTC") (class "Default")
      (node (ref "R1_PINH1") (pin "1") (pinfunction "1_1") (pintype "passive"))
      (node (ref "TP15") (pin "TP") (pinfunction "TP_TP") (pintype "input"))
      (node (ref "U2") (pin "8") (pinfunction "IO0_8") (pintype "bidirectional"))
      (node (ref "U3") (pin "3") (pinfunction "SQW/~{INT}_3") (pintype "output"))
    )
    (net (code "17") (name "IO{slash}BOOT") (class "Default")
      (node (ref "BOOT_BUTTON") (pin "3") (pinfunction "3_3") (pintype "passive"))
      (node (ref "BOOT_BUTTON") (pin "4") (pinfunction "4_4") (pintype "passive"))
      (node (ref "C6") (pin "2") (pinfunction "2_2") (pintype "passive"))
      (node (ref "R_BOOT") (pin "1") (pinfunction "1_1") (pintype "passive"))
      (node (ref "U2") (pin "15") (pinfunction "IO9_15") (pintype "bidirectional"))
    )
    (net (code "18") (name "IO{slash}CHANGE") (class "Default")
      (node (ref "C10") (pin "2") (pinfunction "2_2") (pintype "passive"))
      (node (ref "CHANGE_BUTTON") (pin "3") (pinfunction "3_3") (pintype "passive"))
      (node (ref "CHANGE_BUTTON") (pin "4") (pinfunction "4_4") (pintype "passive"))
      (node (ref "R_CHANGE") (pin "1") (pinfunction "1_1") (pintype "passive"))
      (node (ref "U2") (pin "23") (pinfunction "IO15_23") (pintype "bidirectional"))
    )
    (net (code "19") (name "MISO") (class "Default")
      (node (ref "D12") (pin "2") (pinfunction "2_2") (pintype "passive"))
      (node (ref "J4") (pin "P7") (pinfunction "DAT0_P7") (pintype "bidirectional"))
      (node (ref "R8") (pin "1") (pinfunction "1_1") (pintype "passive"))
      (node (ref "TP6") (pin "TP") (pinfunction "TP_TP") (pintype "input"))
      (node (ref "U1") (pin "2") (pinfunction "DO(IO1)_2") (pintype "bidirectional"))
      (node (ref "U2") (pin "27") (pinfunction "IO2_27") (pintype "bidirectional"))
    )
    (net (code "20") (name "MOSI") (class "Default")
      (node (ref "D11") (pin "2") (pinfunction "2_2") (pintype "passive"))
      (node (ref "J1") (pin "14") (pinfunction "14_14") (pintype "bidirectional"))
      (node (ref "J4") (pin "P3") (pinfunction "CMD_P3") (pintype "bidirectional"))
      (node (ref "R7") (pin "1") (pinfunction "1_1") (pintype "passive"))
      (node (ref "TP7") (pin "TP") (pinfunction "TP_TP") (pintype "input"))
      (node (ref "U1") (pin "5") (pinfunction "DI(IO0)_5") (pintype "bidirectional"))
      (node (ref "U2") (pin "7") (pinfunction "IO7_7") (pintype "bidirectional"))
    )
    (net (code "21") (name "Net-(CHG_LED-PadC)") (class "Default")
      (node (ref "CHG_LED") (pin "C") (pinfunction "C_C") (pintype "passive"))
      (node (ref "R1_BAT") (pin "1") (pinfunction "1_1") (pintype "passive"))
    )
    (net (code "22") (name "Net-(D2-CATHODE)") (class "Default")
      (node (ref "C1_BAT1") (pin "2") (pinfunction "2_2") (pintype "passive"))
      (node (ref "D2") (pin "1") (pinfunction "CATHODE_1") (pintype "bidirectional"))
      (node (ref "IC4") (pin "1") (pinfunction "VIN_1") (pintype "bidirectional"))
      (node (ref "IC4") (pin "3") (pinfunction "CE_3") (pintype "bidirectional"))
      (node (ref "Q1") (pin "2") (pinfunction "S_2") (pintype "bidirectional"))
    )
    (net (code "23") (name "Net-(D3-A)") (class "Default")
      (node (ref "C4") (pin "2") (pinfunction "2_2") (pintype "passive"))
      (node (ref "D3") (pin "2") (pinfunction "A_2") (pintype "bidirectional"))
      (node (ref "D4") (pin "1") (pinfunction "K_1") (pintype "bidirectional"))
    )
    (net (code "24") (name "Net-(D7-CATHODE)") (class "Default")
      (node (ref "D7") (pin "1") (pinfunction "CATHODE_1") (pintype "bidirectional"))
      (node (ref "R_CAPACITOR") (pin "2") (pinfunction "2_2") (pintype "passive"))
    )
    (net (code "25") (name "Net-(EPD_C1-Pad1)") (class "Default")
      (node (ref "EPD_C1") (pin "1") (pinfunction "1_1") (pintype "passive"))
      (node (ref "J1") (pin "4") (pinfunction "4_4") (pintype "bidirectional"))
    )
    (net (code "26") (name "Net-(EPD_C2-Pad1)") (class "Default")
      (node (ref "EPD_C2") (pin "1") (pinfunction "1_1") (pintype "passive"))
      (node (ref "J1") (pin "5") (pinfunction "5_5") (pintype "bidirectional"))
    )
    (net (code "27") (name "Net-(EPD_C6-Pad1)") (class "Default")
      (node (ref "EPD_C6") (pin "1") (pinfunction "1_1") (pintype "passive"))
      (node (ref "J1") (pin "18") (pinfunction "18_18") (pintype "bidirectional"))
    )
    (net (code "28") (name "Net-(EPD_C7-Pad1)") (class "Default")
      (node (ref "EPD_C7") (pin "1") (pinfunction "1_1") (pintype "passive"))
      (node (ref "J1") (pin "19") (pinfunction "19_19") (pintype "bidirectional"))
    )
    (net (code "29") (name "Net-(EPD_C8-Pad1)") (class "Default")
      (node (ref "EPD_C8") (pin "1") (pinfunction "1_1") (pintype "passive"))
      (node (ref "J1") (pin "20") (pinfunction "20_20") (pintype "bidirectional"))
    )
    (net (code "30") (name "Net-(EPD_C10-Pad1)") (class "Default")
      (node (ref "EPD_C10") (pin "1") (pinfunction "1_1") (pintype "passive"))
      (node (ref "J1") (pin "22") (pinfunction "22_22") (pintype "bidirectional"))
    )
    (net (code "31") (name "Net-(EPD_C12-Pad1)") (class "Default")
      (node (ref "EPD_C12") (pin "1") (pinfunction "1_1") (pintype "passive"))
      (node (ref "J1") (pin "24") (pinfunction "24_24") (pintype "bidirectional"))
    )
    (net (code "32") (name "Net-(IC1-CT)") (class "Default")
      (node (ref "C_DELAY") (pin "2") (pinfunction "2_2") (pintype "passive"))
      (node (ref "IC1") (pin "5") (pinfunction "CT_5") (pintype "bidirectional"))
    )
    (net (code "33") (name "Net-(J2-PadA5)") (class "Default")
      (node (ref "J2") (pin "A5") (pinfunction "A5_A5") (pintype "bidirectional"))
      (node (ref "R2-USB1") (pin "2") (pinfunction "2_2") (pintype "passive"))
    )
    (net (code "34") (name "Net-(J2-PadB5)") (class "Default")
      (node (ref "J2") (pin "B5") (pinfunction "B5_B5") (pintype "bidirectional"))
      (node (ref "R2-USB") (pin "1") (pinfunction "1_1") (pintype "passive"))
    )
    (net (code "35") (name "Net-(MCP73831-PROG)") (class "Default")
      (node (ref "MCP73831") (pin "5") (pinfunction "PROG_5") (pintype "input"))
      (node (ref "R2_BAT") (pin "2") (pinfunction "2_2") (pintype "passive"))
    )
    (net (code "36") (name "Net-(MCP73831-STAT)") (class "Default")
      (node (ref "MCP73831") (pin "1") (pinfunction "STAT_1") (pintype "output"))
      (node (ref "R1_BAT") (pin "2") (pinfunction "2_2") (pintype "passive"))
    )
    (net (code "37") (name "PREVGH") (class "Default")
      (node (ref "D5") (pin "1") (pinfunction "K_1") (pintype "bidirectional"))
      (node (ref "EPD_C9") (pin "1") (pinfunction "1_1") (pintype "passive"))
      (node (ref "J1") (pin "21") (pinfunction "21_21") (pintype "bidirectional"))
    )
    (net (code "38") (name "PREVGL") (class "Default")
      (node (ref "D4") (pin "2") (pinfunction "A_2") (pintype "bidirectional"))
      (node (ref "EPD_C11") (pin "1") (pinfunction "1_1") (pintype "passive"))
      (node (ref "J1") (pin "23") (pinfunction "23_23") (pintype "bidirectional"))
    )
    (net (code "39") (name "RESE") (class "Default")
      (node (ref "J1") (pin "3") (pinfunction "3_3") (pintype "bidirectional"))
      (node (ref "Q3") (pin "2") (pinfunction "S_2") (pintype "bidirectional"))
      (node (ref "R3") (pin "2") (pinfunction "2_2") (pintype "passive"))
    )
    (net (code "40") (name "RESE'") (class "Default")
      (node (ref "R2") (pin "2") (pinfunction "2_2") (pintype "passive"))
      (node (ref "R3") (pin "1") (pinfunction "1_1") (pintype "passive"))
      (node (ref "SJ1") (pin "2") (pinfunction "2_2") (pintype "passive"))
    )
    (net (code "41") (name "RESET") (class "Default")
      (node (ref "C5") (pin "2") (pinfunction "2_2") (pintype "passive"))
      (node (ref "IC1") (pin "1") (pinfunction "VOUT_1") (pintype "bidirectional"))
      (node (ref "RESET_BUTTON") (pin "3") (pinfunction "3_3") (pintype "passive"))
      (node (ref "RESET_BUTTON") (pin "4") (pinfunction "4_4") (pintype "passive"))
      (node (ref "R_RESET") (pin "1") (pinfunction "1_1") (pintype "passive"))
      (node (ref "U2") (pin "3") (pinfunction "EN_3") (pintype "input"))
    )
    (net (code "42") (name "RTC_RST") (class "Default")
      (node (ref "U2") (pin "16") (pinfunction "IO18_16") (pintype "bidirectional"))
      (node (ref "U3") (pin "4") (pinfunction "~{RST}_4") (pintype "input"))
    )
    (net (code "43") (name "RX") (class "Default")
      (node (ref "TP2") (pin "TP") (pinfunction "TP_TP") (pintype "input"))
      (node (ref "U2") (pin "24") (pinfunction "RXD0/GPIO17_24") (pintype "bidirectional"))
    )
    (net (code "44") (name "SCK") (class "Default")
      (node (ref "D10") (pin "2") (pinfunction "2_2") (pintype "passive"))
      (node (ref "J1") (pin "13") (pinfunction "13_13") (pintype "bidirectional"))
      (node (ref "J4") (pin "P5") (pinfunction "CLK_P5") (pintype "bidirectional"))
      (node (ref "R6") (pin "1") (pinfunction "1_1") (pintype "passive"))
      (node (ref "TP8") (pin "TP") (pinfunction "TP_TP") (pintype "input"))
      (node (ref "U1") (pin "6") (pinfunction "CLK_6") (pintype "input"))
      (node (ref "U2") (pin "6") (pinfunction "IO6_6") (pintype "bidirectional"))
    )
    (net (code "45") (name "SCL") (class "Default")
      (node (ref "J3") (pin "4") (pinfunction "4_4") (pintype "passive"))
      (node (ref "R2-PINH") (pin "1") (pinfunction "1_1") (pintype "passive"))
      (node (ref "SENSOR2") (pin "4") (pinfunction "SCK_4") (pintype "input"))
      (node (ref "U2") (pin "20") (pinfunction "IO22_20") (pintype "bidirectional"))
      (node (ref "U3") (pin "16") (pinfunction "SCL_16") (pintype "input"))
      (node (ref "U4") (pin "7") (pinfunction "SCL_7") (pintype "input"))
    )
    (net (code "46") (name "SDA") (class "Default")
      (node (ref "J3") (pin "3") (pinfunction "3_3") (pintype "passive"))
      (node (ref "R1_PINH") (pin "1") (pinfunction "1_1") (pintype "passive"))
      (node (ref "SENSOR2") (pin "3") (pinfunction "SDI_3") (pintype "bidirectional"))
      (node (ref "U2") (pin "19") (pinfunction "IO21_19") (pintype "bidirectional"))
      (node (ref "U3") (pin "15") (pinfunction "SDA_15") (pintype "bidirectional"))
      (node (ref "U4") (pin "8") (pinfunction "SDA_8") (pintype "bidirectional"))
    )
    (net (code "47") (name "SRC") (class "Default")
      (node (ref "C4") (pin "1") (pinfunction "1_1") (pintype "passive"))
      (node (ref "D5") (pin "2") (pinfunction "A_2") (pintype "bidirectional"))
      (node (ref "L1") (pin "1") (pinfunction "1_1") (pintype "passive"))
      (node (ref "Q3") (pin "3") (pinfunction "D_3") (pintype "bidirectional"))
    )
    (net (code "48") (name "SS_SD") (class "Default")
      (node (ref "D8") (pin "2") (pinfunction "2_2") (pintype "passive"))
      (node (ref "J4") (pin "P2") (pinfunction "CD/DAT3_P2") (pintype "bidirectional"))
      (node (ref "R10") (pin "1") (pinfunction "1_1") (pintype "passive"))
      (node (ref "U2") (pin "4") (pinfunction "IO4_4") (pintype "bidirectional"))
    )
    (net (code "49") (name "TX") (class "Default")
      (node (ref "TP1") (pin "TP") (pinfunction "TP_TP") (pintype "input"))
      (node (ref "U2") (pin "25") (pinfunction "TXD0/GPIO16_25") (pintype "bidirectional"))
    )
    (net (code "50") (name "USB_D+") (class "Default")
      (node (ref "D1") (pin "1") (pinfunction "I/O1_1_1") (pintype "bidirectional"))
      (node (ref "U2") (pin "14") (pinfunction "IO13_14") (pintype "bidirectional"))
    )
    (net (code "51") (name "USB_D-") (class "Default")
      (node (ref "D1") (pin "3") (pinfunction "I/O2_1_3") (pintype "bidirectional"))
      (node (ref "U2") (pin "13") (pinfunction "IO12_13") (pintype "bidirectional"))
    )
    (net (code "52") (name "VBAT") (class "Default")
      (node (ref "C2_BAT") (pin "2") (pinfunction "2_2") (pintype "passive"))
      (node (ref "MCP73831") (pin "3") (pinfunction "VBAT_3") (pintype "power_in"))
      (node (ref "Q1") (pin "3") (pinfunction "D_3") (pintype "bidirectional"))
      (node (ref "TP3") (pin "TP") (pinfunction "TP_TP") (pintype "input"))
      (node (ref "U4") (pin "2") (pinfunction "CELL_2") (pintype "power_in"))
      (node (ref "U4") (pin "3") (pinfunction "VDD_3") (pintype "power_in"))
    )
    (net (code "53") (name "VBUS") (class "Default")
      (node (ref "C1_BAT") (pin "2") (pinfunction "2_2") (pintype "passive"))
      (node (ref "C4_USB") (pin "2") (pinfunction "2_2") (pintype "passive"))
      (node (ref "C5_USB") (pin "2") (pinfunction "2_2") (pintype "passive"))
      (node (ref "CHG_LED") (pin "A") (pinfunction "A_A") (pintype "passive"))
      (node (ref "D1") (pin "5") (pinfunction "VBUS_5") (pintype "bidirectional"))
      (node (ref "D2") (pin "2") (pinfunction "ANODE_2") (pintype "bidirectional"))
      (node (ref "MCP73831") (pin "4") (pinfunction "VIN_4") (pintype "power_in"))
      (node (ref "PFMF.050.1") (pin "2") (pinfunction "2_2") (pintype "passive"))
      (node (ref "Q1") (pin "1") (pinfunction "G_1") (pintype "bidirectional"))
      (node (ref "R1_PWRUSB") (pin "1") (pinfunction "1_1") (pintype "passive"))
      (node (ref "TP14") (pin "TP") (pinfunction "TP_TP") (pintype "input"))
    )
    (net (code "54") (name "VRTC") (class "Default")
      (node (ref "C10_SUPERCAP") (pin "2") (pinfunction "2_2") (pintype "passive"))
      (node (ref "C8") (pin "1") (pinfunction "1_1") (pintype "passive"))
      (node (ref "R_CAPACITOR") (pin "1") (pinfunction "1_1") (pintype "passive"))
      (node (ref "U3") (pin "14") (pinfunction "VBAT_14") (pintype "power_in"))
    )
    (net (code "55") (name "VUSB") (class "Default")
      (node (ref "J2") (pin "A4") (pinfunction "A4_A4") (pintype "bidirectional"))
      (node (ref "J2") (pin "A9") (pinfunction "A9_A9") (pintype "bidirectional"))
      (node (ref "J2") (pin "B4") (pinfunction "B4_B4") (pintype "bidirectional"))
      (node (ref "J2") (pin "B9") (pinfunction "B9_B9") (pintype "bidirectional"))
      (node (ref "PFMF.050.1") (pin "1") (pinfunction "1_1") (pintype "passive"))
    )
    (net (code "56") (name "unconnected-(IC1-NC-Pad4)") (class "Default")
      (node (ref "IC1") (pin "4") (pinfunction "NC_4") (pintype "no_connect"))
    )
    (net (code "57") (name "unconnected-(IC4-NC-Pad4)") (class "Default")
      (node (ref "IC4") (pin "4") (pinfunction "NC_4") (pintype "no_connect"))
    )
    (net (code "58") (name "unconnected-(J1-Pad1)") (class "Default")
      (node (ref "J1") (pin "1") (pinfunction "1_1") (pintype "bidirectional"))
    )
    (net (code "59") (name "unconnected-(J1-Pad6)") (class "Default")
      (node (ref "J1") (pin "6") (pinfunction "6_6") (pintype "bidirectional"))
    )
    (net (code "60") (name "unconnected-(J1-Pad7)") (class "Default")
      (node (ref "J1") (pin "7") (pinfunction "7_7") (pintype "bidirectional"))
    )
    (net (code "61") (name "unconnected-(J2-PadA8)") (class "Default")
      (node (ref "J2") (pin "A8") (pinfunction "A8_A8") (pintype "bidirectional"))
    )
    (net (code "62") (name "unconnected-(J2-PadB8)") (class "Default")
      (node (ref "J2") (pin "B8") (pinfunction "B8_B8") (pintype "bidirectional"))
    )
    (net (code "63") (name "unconnected-(J4-DAT1-PadP8)") (class "Default")
      (node (ref "J4") (pin "P8") (pinfunction "DAT1_P8") (pintype "bidirectional"))
    )
    (net (code "64") (name "unconnected-(J4-DAT2-PadP1)") (class "Default")
      (node (ref "J4") (pin "P1") (pinfunction "DAT2_P1") (pintype "bidirectional"))
    )
    (net (code "65") (name "unconnected-(J4-DETECTION_1-PadS1)") (class "Default")
      (node (ref "J4") (pin "S1") (pinfunction "DETECTION_1_S1") (pintype "bidirectional"))
    )
    (net (code "66") (name "unconnected-(J4-DETECTION_2-PadS2)") (class "Default")
      (node (ref "J4") (pin "S2") (pinfunction "DETECTION_2_S2") (pintype "bidirectional"))
    )
    (net (code "67") (name "unconnected-(U2-NC-Pad22)") (class "Default")
      (node (ref "U2") (pin "22") (pinfunction "NC_22") (pintype "no_connect"))
    )
    (net (code "68") (name "unconnected-(U4-~{ALERT}-Pad5)") (class "Default")
      (node (ref "U4") (pin "5") (pinfunction "~{ALERT}_5") (pintype "output"))
    )
  )
)
